# Power.net
KiCad netlist of a schematic drawn in Altium Designer
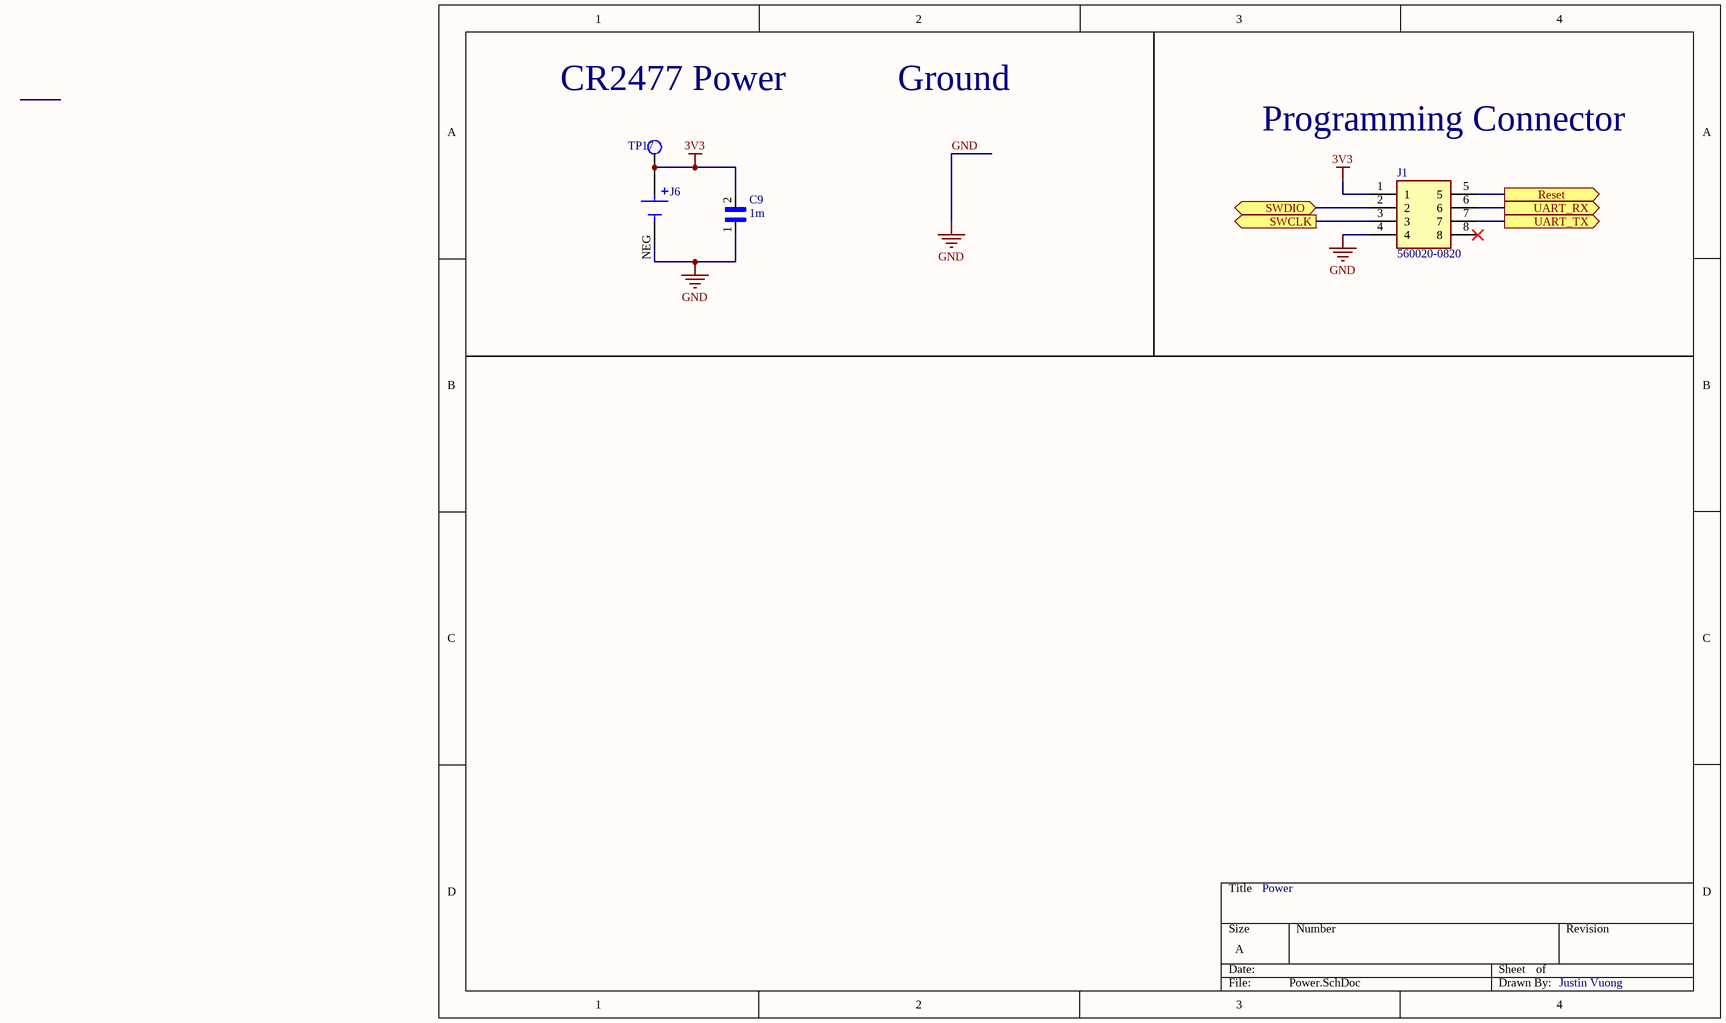
[diagram p0: Power.SchDoc]

(export (version "E")
  (design (tool "Eeschema 10.0.6"))
  (components
    (comp (ref "C9")
      (value "GRM21BR60E107ME15K")
      (footprint "CAPC2012X145N:CAPC2012X145N")
      (description "SMD Capacitor X5R(EIA) with Capacitance: 100uF Tol. 20%. Rated Voltage: 2.5Vdc")
      (libsource (lib "GRM21BR60E107ME15K") (part "GRM21BR60E107ME15K"))
    )
    (comp (ref "J1")
      (value "560020-0820")
      (footprint "SamacSys:560020-0820")
      (description "Connector")
      (fields (field (name "MOUSER PART NUMBER") "538-560020-0820"))
      (libsource (lib "*") (part "560020-0820"))
    )
    (comp (ref "J6")
      (value "BRX1-2477-SM")
      (footprint "BAT_BRX1-2477-SM:BAT_BRX1-2477-SM")
      (description "COIN CELL RETAINER 2477 SMT")
      (fields (field (name "MF") "MPD"))
      (libsource (lib "BRX1-2477-SM") (part "BRX1-2477-SM"))
    )
    (comp (ref "TP17")
      (value "TESTPOINT_LOOP")
      (footprint "PCBComponent_1")
      (description "PC TEST POINT MINIATURE WHITE")
      (libsource (lib "Connectors and Headers") (part "TESTPOINT_LOOP"))
    )
  )
  (nets
    (net (code "1") (name "/Reset") (class "Default")
      (node (ref "J1") (pin "5") (pinfunction "5_5") (pintype "passive"))
    )
    (net (code "2") (name "/SWCLK") (class "Default")
      (node (ref "J1") (pin "3") (pinfunction "3_3") (pintype "passive"))
    )
    (net (code "3") (name "/SWDIO") (class "Default")
      (node (ref "J1") (pin "2") (pinfunction "2_2") (pintype "passive"))
    )
    (net (code "4") (name "/UART_RX") (class "Default")
      (node (ref "J1") (pin "6") (pinfunction "6_6") (pintype "passive"))
    )
    (net (code "5") (name "/UART_TX") (class "Default")
      (node (ref "J1") (pin "7") (pinfunction "7_7") (pintype "passive"))
    )
    (net (code "6") (name "3V3") (class "Default")
      (node (ref "C9") (pin "2") (pinfunction "2_2") (pintype "passive"))
      (node (ref "J1") (pin "1") (pinfunction "1_1") (pintype "passive"))
      (node (ref "J6") (pin "1+") (pinfunction "POS_1+") (pintype "passive"))
      (node (ref "J6") (pin "2+") (pinfunction "POS_2+") (pintype "passive"))
      (node (ref "TP17") (pin "1") (pintype "passive"))
    )
    (net (code "7") (name "GND") (class "Default")
      (node (ref "C9") (pin "1") (pinfunction "1_1") (pintype "passive"))
      (node (ref "J1") (pin "4") (pinfunction "4_4") (pintype "passive"))
      (node (ref "J6") (pin "NEG") (pinfunction "NEG_NEG") (pintype "passive"))
    )
    (net (code "8") (name "unconnected-(J1-Pad8)") (class "Default")
      (node (ref "J1") (pin "8") (pinfunction "8_8") (pintype "passive+no_connect"))
    )
  )
)
